# Sensors.net
KiCad netlist of a schematic drawn in Altium Designer
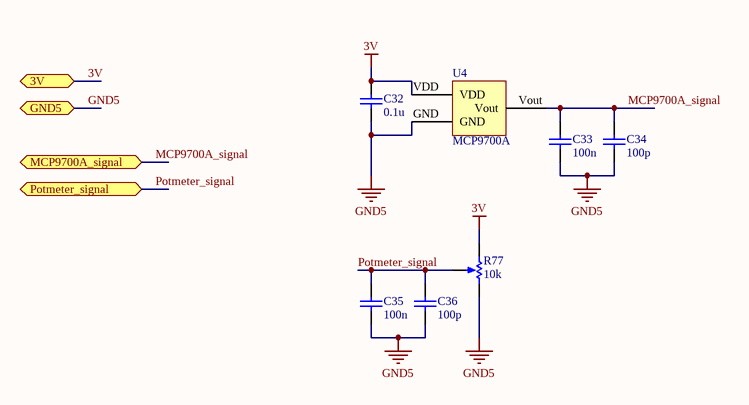
[diagram p0: Sensors.SchDoc]

(export (version "E")
  (design (tool "Eeschema 10.0.6"))
  (components
    (comp (ref "C32")
      (value "0.1u")
      (footprint "dimploma:0805C")
      (libsource (lib "diploma") (part "CAPACITOR"))
    )
    (comp (ref "C33")
      (value "100n")
      (footprint "dimploma:0805C")
      (libsource (lib "diploma") (part "CAPACITOR"))
    )
    (comp (ref "C34")
      (value "100p")
      (footprint "dimploma:0805C")
      (libsource (lib "diploma") (part "CAPACITOR"))
    )
    (comp (ref "C35")
      (value "100n")
      (footprint "dimploma:0805C")
      (libsource (lib "diploma") (part "CAPACITOR"))
    )
    (comp (ref "C36")
      (value "100p")
      (footprint "dimploma:0805C")
      (libsource (lib "diploma") (part "CAPACITOR"))
    )
    (comp (ref "R77")
      (value "10k")
      (footprint "dimploma:TRIM_POT")
      (libsource (lib "diploma") (part "Trim_pot"))
    )
    (comp (ref "U4")
      (value "MCP9700A")
      (footprint "dimploma:TO-92")
      (libsource (lib "diploma") (part "MCP9700A"))
    )
  )
  (nets
    (net (code "1") (name "/MCP9700A_signal") (class "Default")
      (node (ref "C33") (pin "2") (pinfunction "2_2") (pintype "passive"))
      (node (ref "C34") (pin "2") (pinfunction "2_2") (pintype "passive"))
      (node (ref "U4") (pin "Vout") (pinfunction "Vout_Vout") (pintype "passive"))
    )
    (net (code "2") (name "/Potmeter_signal") (class "Default")
      (node (ref "C35") (pin "2") (pinfunction "2_2") (pintype "passive"))
      (node (ref "C36") (pin "2") (pinfunction "2_2") (pintype "passive"))
      (node (ref "R77") (pin "2") (pinfunction "2_2") (pintype "passive"))
    )
    (net (code "3") (name "3V") (class "Default")
      (node (ref "C32") (pin "2") (pinfunction "2_2") (pintype "passive"))
      (node (ref "R77") (pin "1") (pinfunction "1_1") (pintype "passive"))
      (node (ref "U4") (pin "VDD") (pinfunction "VDD_VDD") (pintype "passive"))
    )
    (net (code "4") (name "GND5") (class "Default")
      (node (ref "C32") (pin "1") (pinfunction "1_1") (pintype "passive"))
      (node (ref "C33") (pin "1") (pinfunction "1_1") (pintype "passive"))
      (node (ref "C34") (pin "1") (pinfunction "1_1") (pintype "passive"))
      (node (ref "C35") (pin "1") (pinfunction "1_1") (pintype "passive"))
      (node (ref "C36") (pin "1") (pinfunction "1_1") (pintype "passive"))
      (node (ref "R77") (pin "0") (pinfunction "0_0") (pintype "passive"))
      (node (ref "U4") (pin "GND") (pinfunction "GND_GND") (pintype "passive"))
    )
  )
)
